# IMU.net
KiCad netlist of a schematic drawn in Altium Designer
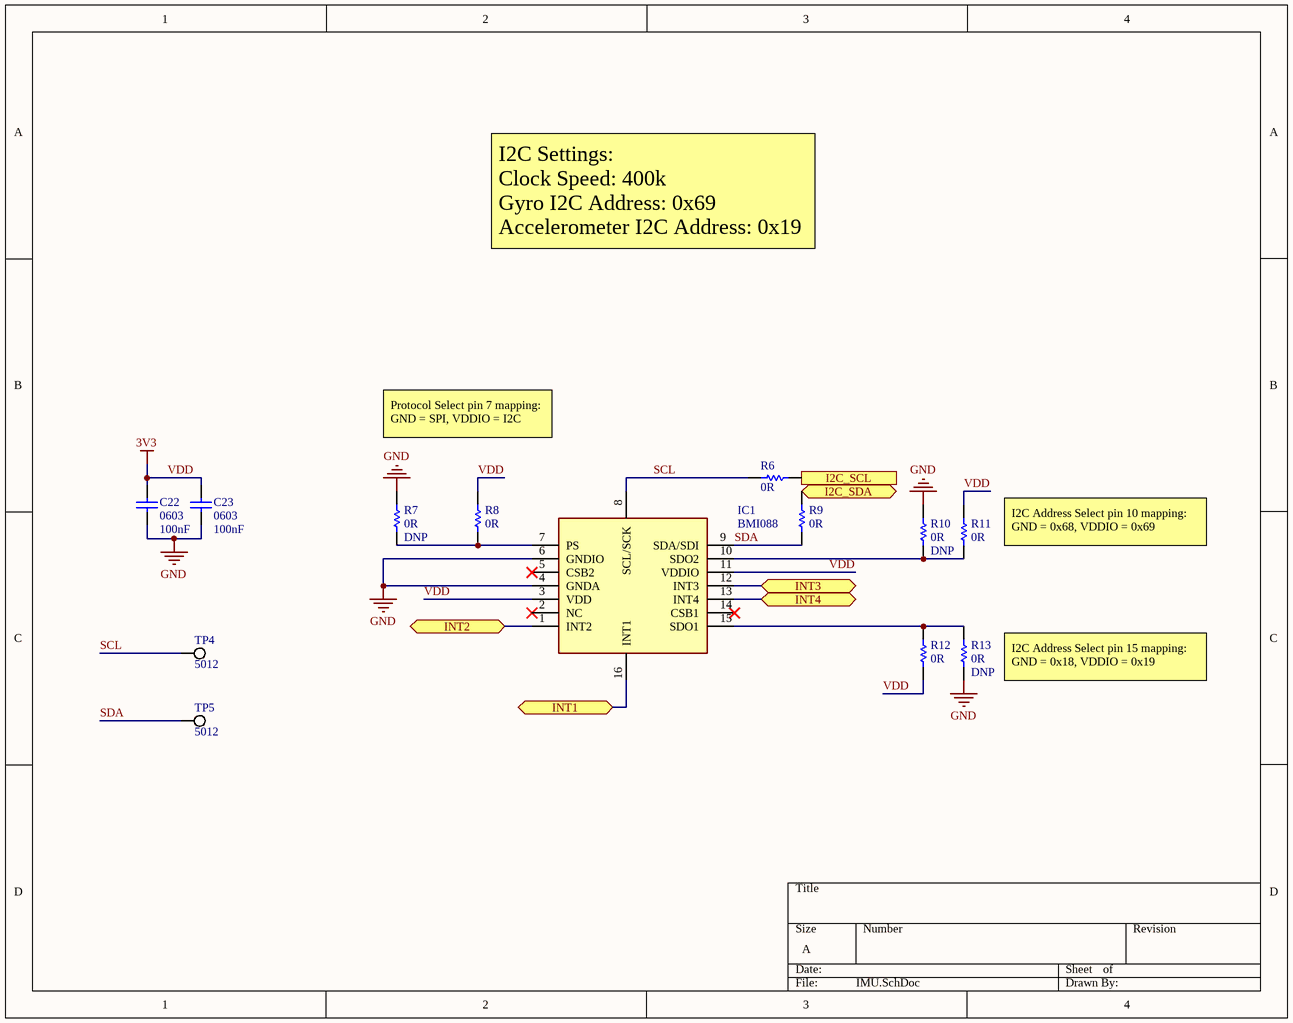
[diagram p0: IMU.SchDoc]

(export (version "E")
  (design (tool "Eeschema 10.0.6"))
  (components
    (comp (ref "C22")
      (value "C0603X104K5RACTU")
      (footprint "CAPC1608X87X35NL15T15")
      (fields
        (field (name "MANUFACTURER") "Kemet")
        (field (name "CASE CODE (IMPERIAL)") "0603")
        (field (name "CAPACITANCE") "100nF")
        (field (name "TOLERANCE") "10%")
        (field (name "VOLTAGE") "50V")
      )
      (libsource (lib "Altium Content Vault") (part "CAP"))
    )
    (comp (ref "C23")
      (value "C0603X104K5RACTU")
      (footprint "CAPC1608X87X35NL15T15")
      (fields
        (field (name "MANUFACTURER") "Kemet")
        (field (name "CASE CODE (IMPERIAL)") "0603")
        (field (name "CAPACITANCE") "100nF")
        (field (name "TOLERANCE") "10%")
        (field (name "VOLTAGE") "50V")
      )
      (libsource (lib "Altium Content Vault") (part "CAP"))
    )
    (comp (ref "IC1")
      (value "BMI088")
      (footprint "SamacSys:BMI088")
      (description "Integrated Circuit")
      (fields (field (name "MOUSER PART NUMBER") "262-BMI088"))
      (libsource (lib "*") (part "BMI088"))
    )
    (comp (ref "R6")
      (value "RC0805JR-100RL")
      (footprint "RESC2013X60X35LL10T20")
      (description "Chip Resistor, 0 Ohm, +/- 5%, 125 mW, -55 to 155 degC, 0805 (2012 Metric), RoHS, Tape and Reel")
      (fields (field (name "MANUFACTURER") "Yageo") (field (name "RESISTANCE") "0R"))
      (libsource (lib "Altium Content Vault") (part "RES-2"))
    )
    (comp (ref "R7")
      (value "RC0805JR-100RL")
      (footprint "RESC2013X60X35LL10T20")
      (description "Chip Resistor, 0 Ohm, +/- 5%, 125 mW, -55 to 155 degC, 0805 (2012 Metric), RoHS, Tape and Reel")
      (fields
        (field (name "MANUFACTURER") "Yageo")
        (field (name "RESISTANCE") "0R")
        (field (name "DNP") "DNP")
      )
      (libsource (lib "Altium Content Vault") (part "RES-2"))
    )
    (comp (ref "R8")
      (value "RC0805JR-100RL")
      (footprint "RESC2013X60X35LL10T20")
      (description "Chip Resistor, 0 Ohm, +/- 5%, 125 mW, -55 to 155 degC, 0805 (2012 Metric), RoHS, Tape and Reel")
      (fields (field (name "MANUFACTURER") "Yageo") (field (name "RESISTANCE") "0R"))
      (libsource (lib "Altium Content Vault") (part "RES-2"))
    )
    (comp (ref "R9")
      (value "RC0805JR-100RL")
      (footprint "RESC2013X60X35LL10T20")
      (description "Chip Resistor, 0 Ohm, +/- 5%, 125 mW, -55 to 155 degC, 0805 (2012 Metric), RoHS, Tape and Reel")
      (fields (field (name "MANUFACTURER") "Yageo") (field (name "RESISTANCE") "0R"))
      (libsource (lib "Altium Content Vault") (part "RES-2"))
    )
    (comp (ref "R10")
      (value "RC0805JR-100RL")
      (footprint "RESC2013X60X35LL10T20")
      (description "Chip Resistor, 0 Ohm, +/- 5%, 125 mW, -55 to 155 degC, 0805 (2012 Metric), RoHS, Tape and Reel")
      (fields
        (field (name "MANUFACTURER") "Yageo")
        (field (name "RESISTANCE") "0R")
        (field (name "DNP") "DNP")
      )
      (libsource (lib "Altium Content Vault") (part "RES-2"))
    )
    (comp (ref "R11")
      (value "RC0805JR-100RL")
      (footprint "RESC2013X60X35LL10T20")
      (description "Chip Resistor, 0 Ohm, +/- 5%, 125 mW, -55 to 155 degC, 0805 (2012 Metric), RoHS, Tape and Reel")
      (fields (field (name "MANUFACTURER") "Yageo") (field (name "RESISTANCE") "0R"))
      (libsource (lib "Altium Content Vault") (part "RES-2"))
    )
    (comp (ref "R12")
      (value "RC0805JR-100RL")
      (footprint "RESC2013X60X35LL10T20")
      (description "Chip Resistor, 0 Ohm, +/- 5%, 125 mW, -55 to 155 degC, 0805 (2012 Metric), RoHS, Tape and Reel")
      (fields (field (name "MANUFACTURER") "Yageo") (field (name "RESISTANCE") "0R"))
      (libsource (lib "Altium Content Vault") (part "RES-2"))
    )
    (comp (ref "R13")
      (value "RC0805JR-100RL")
      (footprint "RESC2013X60X35LL10T20")
      (description "Chip Resistor, 0 Ohm, +/- 5%, 125 mW, -55 to 155 degC, 0805 (2012 Metric), RoHS, Tape and Reel")
      (fields
        (field (name "MANUFACTURER") "Yageo")
        (field (name "RESISTANCE") "0R")
        (field (name "DNP") "DNP")
      )
      (libsource (lib "Altium Content Vault") (part "RES-2"))
    )
    (comp (ref "TP4")
      (value "5012")
      (footprint "KSTN-5012_V")
      (description "Test Point, White, Through Hole, RoHS, Bulk")
      (fields (field (name "MANUFACTURER") "Keystone"))
      (libsource (lib "Altium Content Vault") (part "TESTPOINT_WHITE"))
    )
    (comp (ref "TP5")
      (value "5012")
      (footprint "KSTN-5012_V")
      (description "Test Point, White, Through Hole, RoHS, Bulk")
      (fields (field (name "MANUFACTURER") "Keystone"))
      (libsource (lib "Altium Content Vault") (part "TESTPOINT_WHITE"))
    )
  )
  (nets
    (net (code "1") (name "/I2C_SCL") (class "Default")
      (node (ref "R6") (pin "1") (pinfunction "1_1") (pintype "passive"))
    )
    (net (code "2") (name "/I2C_SDA") (class "Default")
      (node (ref "R9") (pin "2") (pinfunction "2_2") (pintype "passive"))
    )
    (net (code "3") (name "/INT1") (class "Default")
      (node (ref "IC1") (pin "16") (pinfunction "INT1_16") (pintype "passive"))
    )
    (net (code "4") (name "/INT2") (class "Default")
      (node (ref "IC1") (pin "1") (pinfunction "INT2_1") (pintype "passive"))
    )
    (net (code "5") (name "/INT3") (class "Default")
      (node (ref "IC1") (pin "12") (pinfunction "INT3_12") (pintype "passive"))
    )
    (net (code "6") (name "/INT4") (class "Default")
      (node (ref "IC1") (pin "13") (pinfunction "INT4_13") (pintype "passive"))
    )
    (net (code "7") (name "/SCL") (class "Default")
      (node (ref "IC1") (pin "8") (pinfunction "SCL/SCK_8") (pintype "passive"))
      (node (ref "R6") (pin "2") (pinfunction "2_2") (pintype "passive"))
      (node (ref "TP4") (pin "1") (pinfunction "1_1") (pintype "passive"))
    )
    (net (code "8") (name "/SDA") (class "Default")
      (node (ref "IC1") (pin "9") (pinfunction "SDA/SDI_9") (pintype "passive"))
      (node (ref "R9") (pin "1") (pinfunction "1_1") (pintype "passive"))
      (node (ref "TP5") (pin "1") (pinfunction "1_1") (pintype "passive"))
    )
    (net (code "9") (name "3V3") (class "Default")
      (node (ref "C22") (pin "1") (pinfunction "1_1") (pintype "passive"))
      (node (ref "C23") (pin "1") (pinfunction "1_1") (pintype "passive"))
      (node (ref "IC1") (pin "11") (pinfunction "VDDIO_11") (pintype "passive"))
      (node (ref "IC1") (pin "3") (pinfunction "VDD_3") (pintype "passive"))
      (node (ref "R11") (pin "2") (pinfunction "2_2") (pintype "passive"))
      (node (ref "R12") (pin "1") (pinfunction "1_1") (pintype "passive"))
      (node (ref "R8") (pin "2") (pinfunction "2_2") (pintype "passive"))
    )
    (net (code "10") (name "GND") (class "Default")
      (node (ref "C22") (pin "2") (pinfunction "2_2") (pintype "passive"))
      (node (ref "C23") (pin "2") (pinfunction "2_2") (pintype "passive"))
      (node (ref "IC1") (pin "4") (pinfunction "GNDA_4") (pintype "passive"))
      (node (ref "IC1") (pin "6") (pinfunction "GNDIO_6") (pintype "passive"))
      (node (ref "R10") (pin "2") (pinfunction "2_2") (pintype "passive"))
      (node (ref "R13") (pin "1") (pinfunction "1_1") (pintype "passive"))
      (node (ref "R7") (pin "2") (pinfunction "2_2") (pintype "passive"))
    )
    (net (code "11") (name "Net-(IC1-PS)") (class "Default")
      (node (ref "IC1") (pin "7") (pinfunction "PS_7") (pintype "passive"))
      (node (ref "R7") (pin "1") (pinfunction "1_1") (pintype "passive"))
      (node (ref "R8") (pin "1") (pinfunction "1_1") (pintype "passive"))
    )
    (net (code "12") (name "Net-(IC1-SDO1)") (class "Default")
      (node (ref "IC1") (pin "15") (pinfunction "SDO1_15") (pintype "passive"))
      (node (ref "R12") (pin "2") (pinfunction "2_2") (pintype "passive"))
      (node (ref "R13") (pin "2") (pinfunction "2_2") (pintype "passive"))
    )
    (net (code "13") (name "Net-(IC1-SDO2)") (class "Default")
      (node (ref "IC1") (pin "10") (pinfunction "SDO2_10") (pintype "passive"))
      (node (ref "R10") (pin "1") (pinfunction "1_1") (pintype "passive"))
      (node (ref "R11") (pin "1") (pinfunction "1_1") (pintype "passive"))
    )
    (net (code "14") (name "unconnected-(IC1-CSB1-Pad14)") (class "Default")
      (node (ref "IC1") (pin "14") (pinfunction "CSB1_14") (pintype "passive+no_connect"))
    )
    (net (code "15") (name "unconnected-(IC1-CSB2-Pad5)") (class "Default")
      (node (ref "IC1") (pin "5") (pinfunction "CSB2_5") (pintype "passive+no_connect"))
    )
    (net (code "16") (name "unconnected-(IC1-NC-Pad2)") (class "Default")
      (node (ref "IC1") (pin "2") (pinfunction "NC_2") (pintype "passive+no_connect"))
    )
  )
)
